# uSD_mux.net
KiCad netlist of a schematic drawn in EAGLE
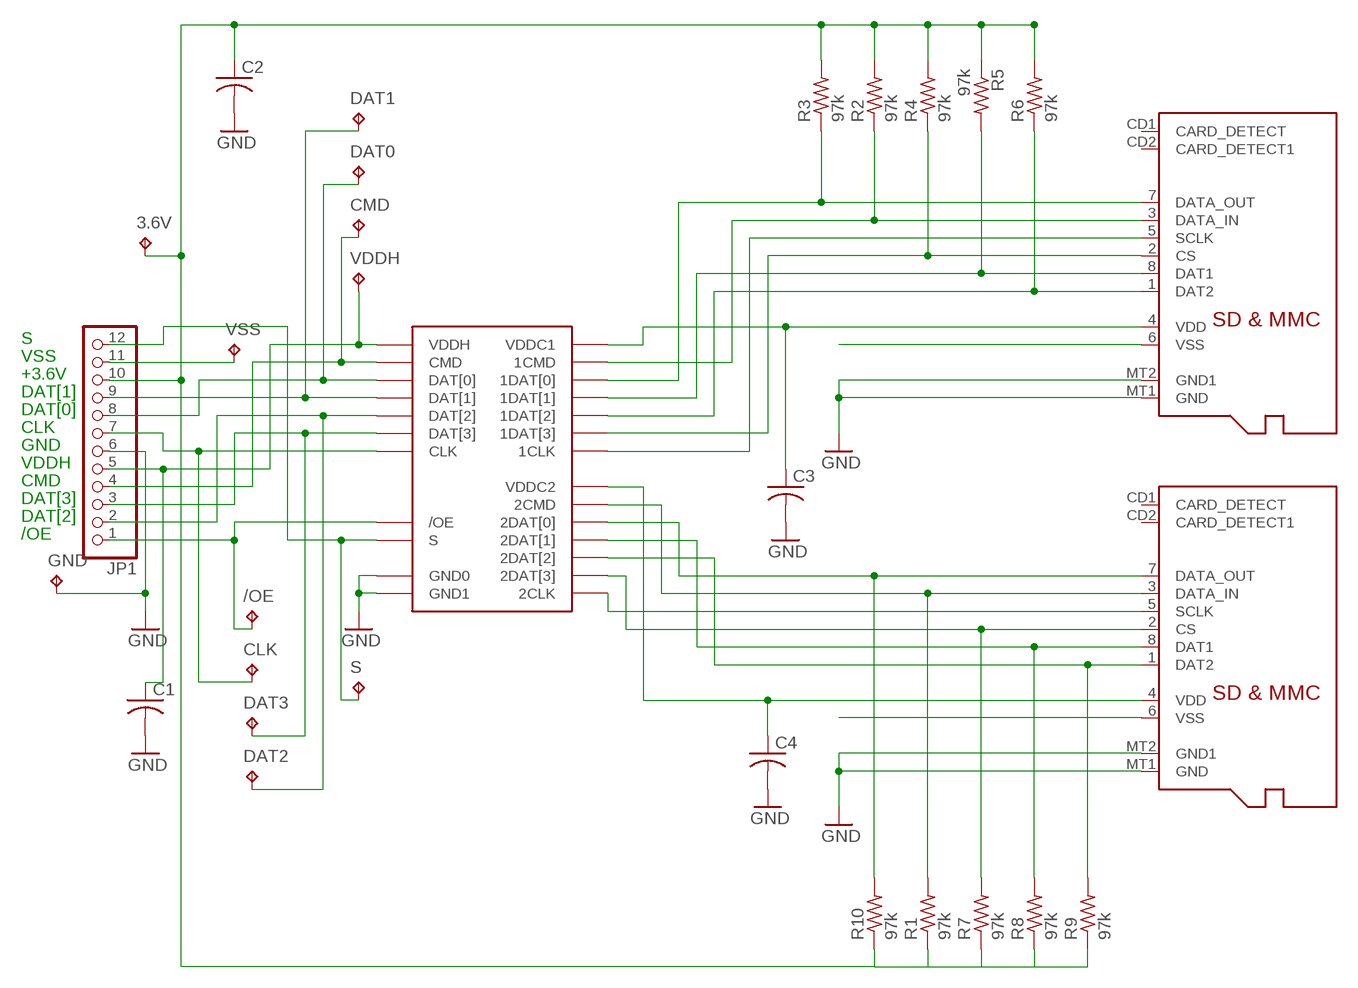
[diagram p0: schematic, sheet 1]

(export (version "E")
  (design (tool "Eeschema 10.0.6"))
  (components
    (comp (ref "+3.6V")
      (value "FSSD06")
      (footprint "eagle-import:MLP-24")
      (libsource (lib "eagle-import") (part "FSSD06"))
    )
    (comp (ref "/OE")
      (value "TPTP20R")
      (footprint "eagle-import:TP20R")
      (libsource (lib "eagle-import") (part "TPTP20R"))
    )
    (comp (ref "3.6V")
      (value "TPTP20R")
      (footprint "eagle-import:TP20R")
      (libsource (lib "eagle-import") (part "TPTP20R"))
    )
    (comp (ref "C1")
      (value "C-USC0805")
      (footprint "eagle-import:C0805")
      (libsource (lib "eagle-import") (part "C-USC0805"))
    )
    (comp (ref "C2")
      (value "C-USC0805")
      (footprint "eagle-import:C0805")
      (libsource (lib "eagle-import") (part "C-USC0805"))
    )
    (comp (ref "C3")
      (value "C-USC0805")
      (footprint "eagle-import:C0805")
      (libsource (lib "eagle-import") (part "C-USC0805"))
    )
    (comp (ref "C4")
      (value "C-USC0805")
      (footprint "eagle-import:C0805")
      (libsource (lib "eagle-import") (part "C-USC0805"))
    )
    (comp (ref "CLK")
      (value "TPTP20R")
      (footprint "eagle-import:TP20R")
      (libsource (lib "eagle-import") (part "TPTP20R"))
    )
    (comp (ref "CMD")
      (value "TPTP20R")
      (footprint "eagle-import:TP20R")
      (libsource (lib "eagle-import") (part "TPTP20R"))
    )
    (comp (ref "DAT0")
      (value "TPTP20R")
      (footprint "eagle-import:TP20R")
      (libsource (lib "eagle-import") (part "TPTP20R"))
    )
    (comp (ref "DAT1")
      (value "TPTP20R")
      (footprint "eagle-import:TP20R")
      (libsource (lib "eagle-import") (part "TPTP20R"))
    )
    (comp (ref "DAT2")
      (value "TPTP20R")
      (footprint "eagle-import:TP20R")
      (libsource (lib "eagle-import") (part "TPTP20R"))
    )
    (comp (ref "DAT3")
      (value "TPTP20R")
      (footprint "eagle-import:TP20R")
      (libsource (lib "eagle-import") (part "TPTP20R"))
    )
    (comp (ref "GND")
      (value "TPTP20R")
      (footprint "eagle-import:TP20R")
      (libsource (lib "eagle-import") (part "TPTP20R"))
    )
    (comp (ref "JP1")
      (value "PINHD-1X12")
      (footprint "eagle-import:1X12")
      (libsource (lib "eagle-import") (part "PINHD-1X12"))
    )
    (comp (ref "R1")
      (value "97k")
      (footprint "eagle-import:R0805")
      (libsource (lib "eagle-import") (part "R-US_R0805"))
    )
    (comp (ref "R2")
      (value "97k")
      (footprint "eagle-import:R0805")
      (libsource (lib "eagle-import") (part "R-US_R0805"))
    )
    (comp (ref "R3")
      (value "97k")
      (footprint "eagle-import:R0805")
      (libsource (lib "eagle-import") (part "R-US_R0805"))
    )
    (comp (ref "R4")
      (value "97k")
      (footprint "eagle-import:R0805")
      (libsource (lib "eagle-import") (part "R-US_R0805"))
    )
    (comp (ref "R5")
      (value "97k")
      (footprint "eagle-import:R0805")
      (libsource (lib "eagle-import") (part "R-US_R0805"))
    )
    (comp (ref "R6")
      (value "97k")
      (footprint "eagle-import:R0805")
      (libsource (lib "eagle-import") (part "R-US_R0805"))
    )
    (comp (ref "R7")
      (value "97k")
      (footprint "eagle-import:R0805")
      (libsource (lib "eagle-import") (part "R-US_R0805"))
    )
    (comp (ref "R8")
      (value "97k")
      (footprint "eagle-import:R0805")
      (libsource (lib "eagle-import") (part "R-US_R0805"))
    )
    (comp (ref "R9")
      (value "97k")
      (footprint "eagle-import:R0805")
      (libsource (lib "eagle-import") (part "R-US_R0805"))
    )
    (comp (ref "R10")
      (value "97k")
      (footprint "eagle-import:R0805")
      (libsource (lib "eagle-import") (part "R-US_R0805"))
    )
    (comp (ref "S")
      (value "TPTP20R")
      (footprint "eagle-import:TP20R")
      (libsource (lib "eagle-import") (part "TPTP20R"))
    )
    (comp (ref "USD1")
      (value "MICROSD")
      (footprint "eagle-import:MICROSD")
      (libsource (lib "eagle-import") (part "MICROSD"))
    )
    (comp (ref "USD2")
      (value "MICROSD")
      (footprint "eagle-import:MICROSD")
      (libsource (lib "eagle-import") (part "MICROSD"))
    )
    (comp (ref "VDDH")
      (value "TPTP20R")
      (footprint "eagle-import:TP20R")
      (libsource (lib "eagle-import") (part "TPTP20R"))
    )
    (comp (ref "VSS")
      (value "TPTP20R")
      (footprint "eagle-import:TP20R")
      (libsource (lib "eagle-import") (part "TPTP20R"))
    )
  )
  (nets
    (net (code "1") (name "/VSS") (class "Default")
      (node (ref "JP1") (pin "11") (pinfunction "11_11") (pintype "passive"))
      (node (ref "USD1") (pin "6") (pinfunction "VSS_6") (pintype "power_in"))
      (node (ref "USD2") (pin "6") (pinfunction "VSS_6") (pintype "power_in"))
      (node (ref "VSS") (pin "TP") (pinfunction "TP_TP") (pintype "input"))
    )
    (net (code "2") (name "GND") (class "Default")
      (node (ref "+3.6V") (pin "GND0") (pinfunction "GND0_GND0") (pintype "bidirectional"))
      (node (ref "+3.6V") (pin "GND1") (pinfunction "GND1_GND1") (pintype "bidirectional"))
      (node (ref "C1") (pin "2") (pinfunction "2_2") (pintype "passive"))
      (node (ref "C2") (pin "2") (pinfunction "2_2") (pintype "passive"))
      (node (ref "C3") (pin "2") (pinfunction "2_2") (pintype "passive"))
      (node (ref "C4") (pin "2") (pinfunction "2_2") (pintype "passive"))
      (node (ref "GND") (pin "TP") (pinfunction "TP_TP") (pintype "input"))
      (node (ref "JP1") (pin "6") (pinfunction "6_6") (pintype "passive"))
      (node (ref "USD1") (pin "MT1") (pinfunction "GND_MT1") (pintype "power_in"))
      (node (ref "USD1") (pin "MT2") (pinfunction "GND1_MT2") (pintype "power_in"))
      (node (ref "USD2") (pin "MT1") (pinfunction "GND_MT1") (pintype "power_in"))
      (node (ref "USD2") (pin "MT2") (pinfunction "GND1_MT2") (pintype "power_in"))
    )
    (net (code "3") (name "Net-(+3.6V-2CLK)") (class "Default")
      (node (ref "+3.6V") (pin "2CLCK") (pinfunction "2CLK_2CLCK") (pintype "bidirectional"))
      (node (ref "USD2") (pin "5") (pinfunction "SCLK_5") (pintype "input"))
    )
    (net (code "4") (name "Net-(+3.6V-PadCLK)") (class "Default")
      (node (ref "+3.6V") (pin "CLK") (pinfunction "CLK_CLK") (pintype "bidirectional"))
      (node (ref "CLK") (pin "TP") (pinfunction "TP_TP") (pintype "input"))
      (node (ref "JP1") (pin "7") (pinfunction "7_7") (pintype "passive"))
    )
    (net (code "5") (name "Net-(+3.6V-PadCMD)") (class "Default")
      (node (ref "+3.6V") (pin "CMD") (pinfunction "CMD_CMD") (pintype "bidirectional"))
      (node (ref "CMD") (pin "TP") (pinfunction "TP_TP") (pintype "input"))
      (node (ref "JP1") (pin "4") (pinfunction "4_4") (pintype "passive"))
    )
    (net (code "6") (name "Net-(+3.6V-PadDAT[0])") (class "Default")
      (node (ref "+3.6V") (pin "DAT[0]") (pinfunction "DAT[0]_DAT[0]") (pintype "bidirectional"))
      (node (ref "DAT0") (pin "TP") (pinfunction "TP_TP") (pintype "input"))
      (node (ref "JP1") (pin "8") (pinfunction "8_8") (pintype "passive"))
    )
    (net (code "7") (name "Net-(+3.6V-PadDAT[1])") (class "Default")
      (node (ref "+3.6V") (pin "DAT[1]") (pinfunction "DAT[1]_DAT[1]") (pintype "bidirectional"))
      (node (ref "DAT1") (pin "TP") (pinfunction "TP_TP") (pintype "input"))
      (node (ref "JP1") (pin "9") (pinfunction "9_9") (pintype "passive"))
    )
    (net (code "8") (name "Net-(+3.6V-PadDAT[2])") (class "Default")
      (node (ref "+3.6V") (pin "DAT[2]") (pinfunction "DAT[2]_DAT[2]") (pintype "bidirectional"))
      (node (ref "DAT2") (pin "TP") (pinfunction "TP_TP") (pintype "input"))
      (node (ref "JP1") (pin "2") (pinfunction "2_2") (pintype "passive"))
    )
    (net (code "9") (name "Net-(+3.6V-PadDAT[3])") (class "Default")
      (node (ref "+3.6V") (pin "DAT[3]") (pinfunction "DAT[3]_DAT[3]") (pintype "bidirectional"))
      (node (ref "DAT3") (pin "TP") (pinfunction "TP_TP") (pintype "input"))
      (node (ref "JP1") (pin "3") (pinfunction "3_3") (pintype "passive"))
    )
    (net (code "10") (name "Net-(+3.6V-PadS)") (class "Default")
      (node (ref "+3.6V") (pin "S") (pinfunction "S_S") (pintype "bidirectional"))
      (node (ref "JP1") (pin "12") (pinfunction "12_12") (pintype "passive"))
      (node (ref "S") (pin "TP") (pinfunction "TP_TP") (pintype "input"))
    )
    (net (code "11") (name "Net-(+3.6V-PadVDDH)") (class "Default")
      (node (ref "+3.6V") (pin "VDDH") (pinfunction "VDDH_VDDH") (pintype "bidirectional"))
      (node (ref "C1") (pin "1") (pinfunction "1_1") (pintype "passive"))
      (node (ref "JP1") (pin "5") (pinfunction "5_5") (pintype "passive"))
      (node (ref "VDDH") (pin "TP") (pinfunction "TP_TP") (pintype "input"))
    )
    (net (code "12") (name "Net-(+3.6V-Pad{slash}OE)") (class "Default")
      (node (ref "+3.6V") (pin "/OE") (pinfunction "/OE_/OE") (pintype "bidirectional"))
      (node (ref "/OE") (pin "TP") (pinfunction "TP_TP") (pintype "input"))
      (node (ref "JP1") (pin "1") (pinfunction "1_1") (pintype "passive"))
    )
    (net (code "13") (name "Net-(3.6V-PadTP)") (class "Default")
      (node (ref "3.6V") (pin "TP") (pinfunction "TP_TP") (pintype "input"))
      (node (ref "C2") (pin "1") (pinfunction "1_1") (pintype "passive"))
      (node (ref "JP1") (pin "10") (pinfunction "10_10") (pintype "passive"))
      (node (ref "R1") (pin "1") (pinfunction "1_1") (pintype "passive"))
      (node (ref "R10") (pin "1") (pinfunction "1_1") (pintype "passive"))
      (node (ref "R2") (pin "2") (pinfunction "2_2") (pintype "passive"))
      (node (ref "R3") (pin "2") (pinfunction "2_2") (pintype "passive"))
      (node (ref "R4") (pin "2") (pinfunction "2_2") (pintype "passive"))
      (node (ref "R5") (pin "1") (pinfunction "1_1") (pintype "passive"))
      (node (ref "R6") (pin "2") (pinfunction "2_2") (pintype "passive"))
      (node (ref "R7") (pin "1") (pinfunction "1_1") (pintype "passive"))
      (node (ref "R8") (pin "1") (pinfunction "1_1") (pintype "passive"))
      (node (ref "R9") (pin "1") (pinfunction "1_1") (pintype "passive"))
    )
    (net (code "14") (name "Net-(USD1-CS)") (class "Default")
      (node (ref "+3.6V") (pin "1DAT[3]") (pinfunction "1DAT[3]_1DAT[3]") (pintype "bidirectional"))
      (node (ref "R4") (pin "1") (pinfunction "1_1") (pintype "passive"))
      (node (ref "USD1") (pin "2") (pinfunction "CS_2") (pintype "input"))
    )
    (net (code "15") (name "Net-(USD1-DAT1)") (class "Default")
      (node (ref "+3.6V") (pin "1DAT[1]") (pinfunction "1DAT[1]_1DAT[1]") (pintype "bidirectional"))
      (node (ref "R5") (pin "2") (pinfunction "2_2") (pintype "passive"))
      (node (ref "USD1") (pin "8") (pinfunction "DAT1_8") (pintype "bidirectional"))
    )
    (net (code "16") (name "Net-(USD1-DAT2)") (class "Default")
      (node (ref "+3.6V") (pin "1DAT[2]") (pinfunction "1DAT[2]_1DAT[2]") (pintype "bidirectional"))
      (node (ref "R6") (pin "1") (pinfunction "1_1") (pintype "passive"))
      (node (ref "USD1") (pin "1") (pinfunction "DAT2_1") (pintype "bidirectional"))
    )
    (net (code "17") (name "Net-(USD1-DATA_IN)") (class "Default")
      (node (ref "+3.6V") (pin "1CMD") (pinfunction "1CMD_1CMD") (pintype "bidirectional"))
      (node (ref "R2") (pin "1") (pinfunction "1_1") (pintype "passive"))
      (node (ref "USD1") (pin "3") (pinfunction "DATA_IN_3") (pintype "input"))
    )
    (net (code "18") (name "Net-(USD1-DATA_OUT)") (class "Default")
      (node (ref "+3.6V") (pin "1DAT[0]") (pinfunction "1DAT[0]_1DAT[0]") (pintype "bidirectional"))
      (node (ref "R3") (pin "1") (pinfunction "1_1") (pintype "passive"))
      (node (ref "USD1") (pin "7") (pinfunction "DATA_OUT_7") (pintype "output"))
    )
    (net (code "19") (name "Net-(USD1-SCLK)") (class "Default")
      (node (ref "+3.6V") (pin "1CLK") (pinfunction "1CLK_1CLK") (pintype "bidirectional"))
      (node (ref "USD1") (pin "5") (pinfunction "SCLK_5") (pintype "input"))
    )
    (net (code "20") (name "Net-(USD1-VDD)") (class "Default")
      (node (ref "+3.6V") (pin "VDDC1") (pinfunction "VDDC1_VDDC1") (pintype "bidirectional"))
      (node (ref "C3") (pin "1") (pinfunction "1_1") (pintype "passive"))
      (node (ref "USD1") (pin "4") (pinfunction "VDD_4") (pintype "power_in"))
    )
    (net (code "21") (name "Net-(USD2-CS)") (class "Default")
      (node (ref "+3.6V") (pin "2DAT[3]") (pinfunction "2DAT[3]_2DAT[3]") (pintype "bidirectional"))
      (node (ref "R7") (pin "2") (pinfunction "2_2") (pintype "passive"))
      (node (ref "USD2") (pin "2") (pinfunction "CS_2") (pintype "input"))
    )
    (net (code "22") (name "Net-(USD2-DAT1)") (class "Default")
      (node (ref "+3.6V") (pin "2DAT[1]") (pinfunction "2DAT[1]_2DAT[1]") (pintype "bidirectional"))
      (node (ref "R8") (pin "2") (pinfunction "2_2") (pintype "passive"))
      (node (ref "USD2") (pin "8") (pinfunction "DAT1_8") (pintype "bidirectional"))
    )
    (net (code "23") (name "Net-(USD2-DAT2)") (class "Default")
      (node (ref "+3.6V") (pin "2DAT[2]") (pinfunction "2DAT[2]_2DAT[2]") (pintype "bidirectional"))
      (node (ref "R9") (pin "2") (pinfunction "2_2") (pintype "passive"))
      (node (ref "USD2") (pin "1") (pinfunction "DAT2_1") (pintype "bidirectional"))
    )
    (net (code "24") (name "Net-(USD2-DATA_IN)") (class "Default")
      (node (ref "+3.6V") (pin "2CMD") (pinfunction "2CMD_2CMD") (pintype "bidirectional"))
      (node (ref "R1") (pin "2") (pinfunction "2_2") (pintype "passive"))
      (node (ref "USD2") (pin "3") (pinfunction "DATA_IN_3") (pintype "input"))
    )
    (net (code "25") (name "Net-(USD2-DATA_OUT)") (class "Default")
      (node (ref "+3.6V") (pin "2DAT[0]") (pinfunction "2DAT[0]_2DAT[0]") (pintype "bidirectional"))
      (node (ref "R10") (pin "2") (pinfunction "2_2") (pintype "passive"))
      (node (ref "USD2") (pin "7") (pinfunction "DATA_OUT_7") (pintype "output"))
    )
    (net (code "26") (name "Net-(USD2-VDD)") (class "Default")
      (node (ref "+3.6V") (pin "VDDC2") (pinfunction "VDDC2_VDDC2") (pintype "bidirectional"))
      (node (ref "C4") (pin "1") (pinfunction "1_1") (pintype "passive"))
      (node (ref "USD2") (pin "4") (pinfunction "VDD_4") (pintype "power_in"))
    )
    (net (code "27") (name "unconnected-(USD1-CARD_DETECT-PadCD1)") (class "Default")
      (node (ref "USD1") (pin "CD1") (pinfunction "CARD_DETECT_CD1") (pintype "passive"))
    )
    (net (code "28") (name "unconnected-(USD1-CARD_DETECT1-PadCD2)") (class "Default")
      (node (ref "USD1") (pin "CD2") (pinfunction "CARD_DETECT1_CD2") (pintype "passive"))
    )
    (net (code "29") (name "unconnected-(USD2-CARD_DETECT-PadCD1)") (class "Default")
      (node (ref "USD2") (pin "CD1") (pinfunction "CARD_DETECT_CD1") (pintype "passive"))
    )
    (net (code "30") (name "unconnected-(USD2-CARD_DETECT1-PadCD2)") (class "Default")
      (node (ref "USD2") (pin "CD2") (pinfunction "CARD_DETECT1_CD2") (pintype "passive"))
    )
  )
)
